# Poseidon.net
KiCad netlist of a schematic drawn in EAGLE
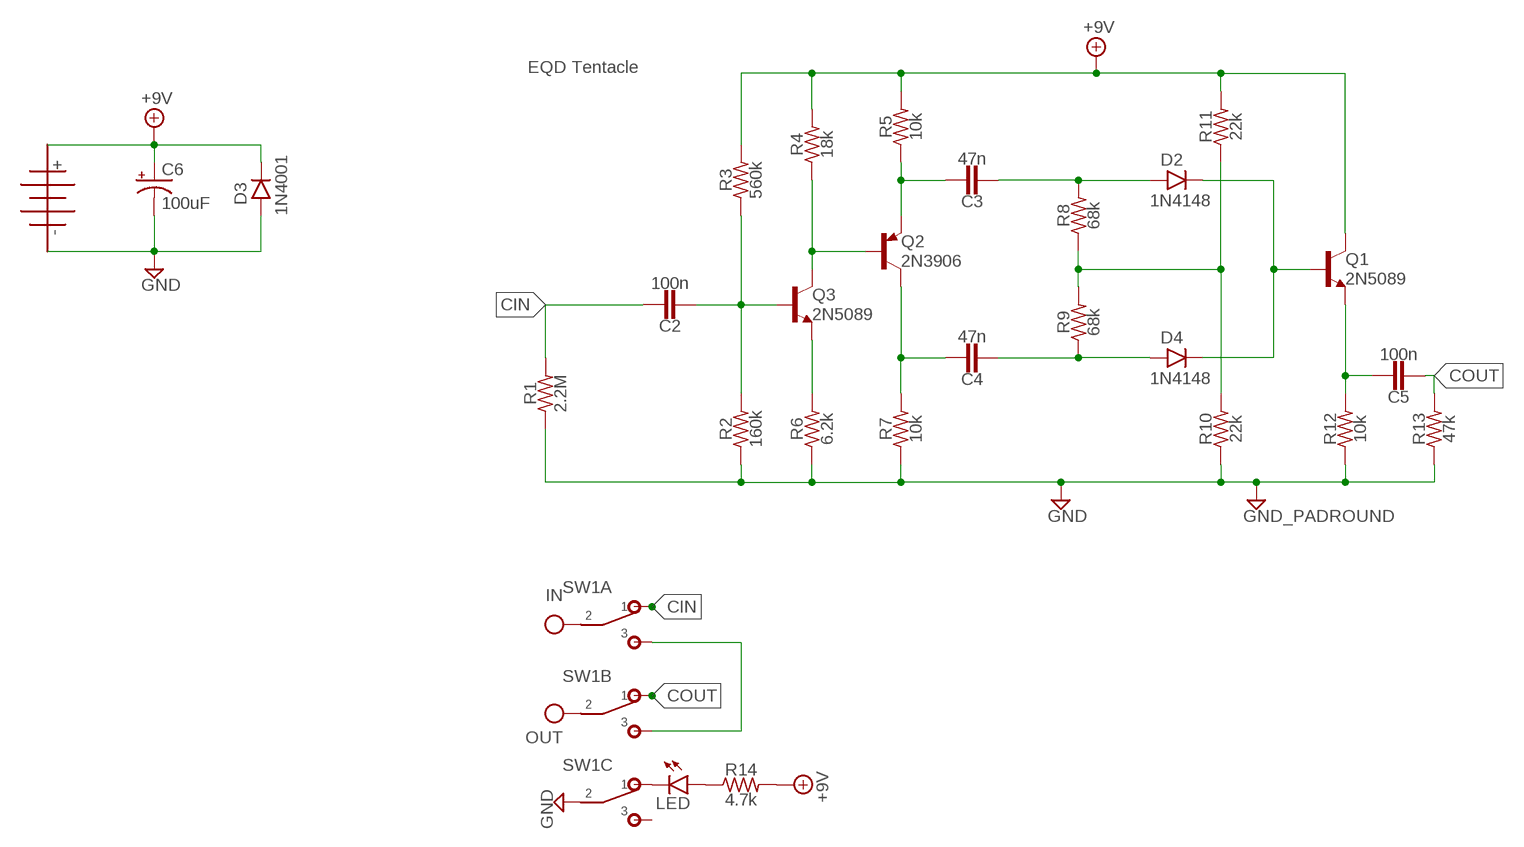
[diagram p0: schematic, sheet 1]

(export (version "E")
  (design (tool "Eeschema 10.0.6"))
  (components
    (comp (ref "C2")
      (value "100n")
      (footprint "eagle-import:0.2_.SML")
      (libsource (lib "eagle-import") (part "CAP.2"))
    )
    (comp (ref "C3")
      (value "47n")
      (footprint "eagle-import:0.2_.SML")
      (libsource (lib "eagle-import") (part "CAP.2"))
    )
    (comp (ref "C4")
      (value "47n")
      (footprint "eagle-import:0.2_.SML")
      (libsource (lib "eagle-import") (part "CAP.2"))
    )
    (comp (ref "C5")
      (value "100n")
      (footprint "eagle-import:0.2_.SML")
      (libsource (lib "eagle-import") (part "CAP.2"))
    )
    (comp (ref "C6")
      (value "100uF")
      (footprint "eagle-import:063_025")
      (libsource (lib "eagle-import") (part "0631"))
    )
    (comp (ref "D2")
      (value "1N4148")
      (footprint "eagle-import:DO35-3")
      (libsource (lib "eagle-import") (part "DO35.3"))
    )
    (comp (ref "D3")
      (value "1N4001")
      (footprint "eagle-import:DO41-3")
      (libsource (lib "eagle-import") (part "DO41.3"))
    )
    (comp (ref "D4")
      (value "1N4148")
      (footprint "eagle-import:DO35-3")
      (libsource (lib "eagle-import") (part "DO35.3"))
    )
    (comp (ref "DC")
      (value "BATTERYBAT2")
      (footprint "eagle-import:BATTERY2")
      (libsource (lib "eagle-import") (part "BATTERYBAT2"))
    )
    (comp (ref "GND")
      (value "GND_PADROUND")
      (footprint "eagle-import:ROUND")
      (libsource (lib "eagle-import") (part "GND_PADROUND"))
    )
    (comp (ref "IN")
      (value "IN")
      (footprint "eagle-import:SQUARE")
      (libsource (lib "eagle-import") (part "IN"))
    )
    (comp (ref "LED")
      (value "LED3MM")
      (footprint "eagle-import:LED3MM")
      (libsource (lib "eagle-import") (part "LED3MM"))
    )
    (comp (ref "OUT")
      (value "OUT")
      (footprint "eagle-import:SQUARE")
      (libsource (lib "eagle-import") (part "OUT"))
    )
    (comp (ref "Q1")
      (value "2N5089")
      (footprint "eagle-import:TO92")
      (libsource (lib "eagle-import") (part "2N5088"))
    )
    (comp (ref "Q2")
      (value "2N3906")
      (footprint "eagle-import:TO92")
      (libsource (lib "eagle-import") (part "2N5087"))
    )
    (comp (ref "Q3")
      (value "2N5089")
      (footprint "eagle-import:TO92")
      (libsource (lib "eagle-import") (part "2N5088"))
    )
    (comp (ref "R1")
      (value "2.2M")
      (footprint "eagle-import:0.3_.B")
      (libsource (lib "eagle-import") (part "R.3B"))
    )
    (comp (ref "R2")
      (value "160k")
      (footprint "eagle-import:0.3_.B")
      (libsource (lib "eagle-import") (part "R.3B"))
    )
    (comp (ref "R3")
      (value "560k")
      (footprint "eagle-import:0.3_.B")
      (libsource (lib "eagle-import") (part "R.3B"))
    )
    (comp (ref "R4")
      (value "18k")
      (footprint "eagle-import:0.3_.B")
      (libsource (lib "eagle-import") (part "R.3B"))
    )
    (comp (ref "R5")
      (value "10k")
      (footprint "eagle-import:0.3_.B")
      (libsource (lib "eagle-import") (part "R.3B"))
    )
    (comp (ref "R6")
      (value "6.2k")
      (footprint "eagle-import:0.3_.B")
      (libsource (lib "eagle-import") (part "R.3B"))
    )
    (comp (ref "R7")
      (value "10k")
      (footprint "eagle-import:0.3_.B")
      (libsource (lib "eagle-import") (part "R.3B"))
    )
    (comp (ref "R8")
      (value "68k")
      (footprint "eagle-import:0.3_.B")
      (libsource (lib "eagle-import") (part "R.3B"))
    )
    (comp (ref "R9")
      (value "68k")
      (footprint "eagle-import:0.3_.B")
      (libsource (lib "eagle-import") (part "R.3B"))
    )
    (comp (ref "R10")
      (value "22k")
      (footprint "eagle-import:0.3_.B")
      (libsource (lib "eagle-import") (part "R.3B"))
    )
    (comp (ref "R11")
      (value "22k")
      (footprint "eagle-import:0.3_.B")
      (libsource (lib "eagle-import") (part "R.3B"))
    )
    (comp (ref "R12")
      (value "10k")
      (footprint "eagle-import:0.3_.B")
      (libsource (lib "eagle-import") (part "R.3B"))
    )
    (comp (ref "R13")
      (value "47k")
      (footprint "eagle-import:0.3_.B")
      (libsource (lib "eagle-import") (part "R.3B"))
    )
    (comp (ref "R14")
      (value "4.7k")
      (footprint "eagle-import:0.3_.B")
      (libsource (lib "eagle-import") (part "R.3B"))
    )
    (comp (ref "SW1")
      (value "3PDT")
      (footprint "eagle-import:3PDT")
      (libsource (lib "eagle-import") (part "3PDT"))
    )
  )
  (nets
    (net (code "1") (name "+9V") (class "Default")
      (node (ref "C6") (pin "+") (pinfunction "+_+") (pintype "passive"))
      (node (ref "D3") (pin "C") (pinfunction "C_C") (pintype "passive"))
      (node (ref "DC") (pin "P$1") (pinfunction "P$1_P$1") (pintype "bidirectional"))
      (node (ref "Q1") (pin "1") (pinfunction "C_1") (pintype "passive"))
      (node (ref "R11") (pin "2") (pinfunction "2_2") (pintype "passive"))
      (node (ref "R14") (pin "2") (pinfunction "2_2") (pintype "passive"))
      (node (ref "R3") (pin "2") (pinfunction "2_2") (pintype "passive"))
      (node (ref "R4") (pin "2") (pinfunction "2_2") (pintype "passive"))
      (node (ref "R5") (pin "2") (pinfunction "2_2") (pintype "passive"))
    )
    (net (code "2") (name "CIN") (class "Default")
      (node (ref "C2") (pin "1") (pinfunction "1_1") (pintype "passive"))
      (node (ref "R1") (pin "2") (pinfunction "2_2") (pintype "passive"))
      (node (ref "SW1") (pin "A1") (pinfunction "1_A1") (pintype "passive"))
    )
    (net (code "3") (name "COUT") (class "Default")
      (node (ref "C5") (pin "2") (pinfunction "2_2") (pintype "passive"))
      (node (ref "R13") (pin "2") (pinfunction "2_2") (pintype "passive"))
      (node (ref "SW1") (pin "B1") (pinfunction "1_B1") (pintype "passive"))
    )
    (net (code "4") (name "GND") (class "Default")
      (node (ref "C6") (pin "-") (pinfunction "-_-") (pintype "passive"))
      (node (ref "D3") (pin "A") (pinfunction "A_A") (pintype "passive"))
      (node (ref "DC") (pin "P$2") (pinfunction "P$2_P$2") (pintype "bidirectional"))
      (node (ref "GND") (pin "1") (pinfunction "GND_1") (pintype "power_in"))
      (node (ref "R1") (pin "1") (pinfunction "1_1") (pintype "passive"))
      (node (ref "R10") (pin "1") (pinfunction "1_1") (pintype "passive"))
      (node (ref "R12") (pin "1") (pinfunction "1_1") (pintype "passive"))
      (node (ref "R13") (pin "1") (pinfunction "1_1") (pintype "passive"))
      (node (ref "R2") (pin "1") (pinfunction "1_1") (pintype "passive"))
      (node (ref "R6") (pin "1") (pinfunction "1_1") (pintype "passive"))
      (node (ref "R7") (pin "1") (pinfunction "1_1") (pintype "passive"))
      (node (ref "SW1") (pin "C2") (pinfunction "2_C2") (pintype "passive"))
    )
    (net (code "5") (name "IN") (class "Default")
      (node (ref "IN") (pin "1") (pinfunction "IN_1") (pintype "power_in"))
      (node (ref "SW1") (pin "A2") (pinfunction "2_A2") (pintype "passive"))
    )
    (net (code "6") (name "Net-(C3-Pad2)") (class "Default")
      (node (ref "C3") (pin "2") (pinfunction "2_2") (pintype "passive"))
      (node (ref "D2") (pin "A") (pinfunction "A_A") (pintype "passive"))
      (node (ref "R8") (pin "2") (pinfunction "2_2") (pintype "passive"))
    )
    (net (code "7") (name "Net-(C4-Pad2)") (class "Default")
      (node (ref "C4") (pin "2") (pinfunction "2_2") (pintype "passive"))
      (node (ref "D4") (pin "A") (pinfunction "A_A") (pintype "passive"))
      (node (ref "R9") (pin "1") (pinfunction "1_1") (pintype "passive"))
    )
    (net (code "8") (name "Net-(LED-C)") (class "Default")
      (node (ref "LED") (pin "K") (pinfunction "C_K") (pintype "passive"))
      (node (ref "SW1") (pin "C1") (pinfunction "1_C1") (pintype "passive"))
    )
    (net (code "9") (name "Net-(LED-PadA)") (class "Default")
      (node (ref "LED") (pin "A") (pinfunction "A_A") (pintype "passive"))
      (node (ref "R14") (pin "1") (pinfunction "1_1") (pintype "passive"))
    )
    (net (code "10") (name "Net-(Q1-B)") (class "Default")
      (node (ref "D2") (pin "C") (pinfunction "C_C") (pintype "passive"))
      (node (ref "D4") (pin "C") (pinfunction "C_C") (pintype "passive"))
      (node (ref "Q1") (pin "2") (pinfunction "B_2") (pintype "passive"))
    )
    (net (code "11") (name "Net-(Q1-E)") (class "Default")
      (node (ref "C5") (pin "1") (pinfunction "1_1") (pintype "passive"))
      (node (ref "Q1") (pin "3") (pinfunction "E_3") (pintype "passive"))
      (node (ref "R12") (pin "2") (pinfunction "2_2") (pintype "passive"))
    )
    (net (code "12") (name "Net-(Q2-B)") (class "Default")
      (node (ref "Q2") (pin "2") (pinfunction "B_2") (pintype "passive"))
      (node (ref "Q3") (pin "1") (pinfunction "C_1") (pintype "passive"))
      (node (ref "R4") (pin "1") (pinfunction "1_1") (pintype "passive"))
    )
    (net (code "13") (name "Net-(Q2-C)") (class "Default")
      (node (ref "C4") (pin "1") (pinfunction "1_1") (pintype "passive"))
      (node (ref "Q2") (pin "1") (pinfunction "C_1") (pintype "passive"))
      (node (ref "R7") (pin "2") (pinfunction "2_2") (pintype "passive"))
    )
    (net (code "14") (name "Net-(Q2-E)") (class "Default")
      (node (ref "C3") (pin "1") (pinfunction "1_1") (pintype "passive"))
      (node (ref "Q2") (pin "3") (pinfunction "E_3") (pintype "passive"))
      (node (ref "R5") (pin "1") (pinfunction "1_1") (pintype "passive"))
    )
    (net (code "15") (name "Net-(Q3-B)") (class "Default")
      (node (ref "C2") (pin "2") (pinfunction "2_2") (pintype "passive"))
      (node (ref "Q3") (pin "2") (pinfunction "B_2") (pintype "passive"))
      (node (ref "R2") (pin "2") (pinfunction "2_2") (pintype "passive"))
      (node (ref "R3") (pin "1") (pinfunction "1_1") (pintype "passive"))
    )
    (net (code "16") (name "Net-(Q3-E)") (class "Default")
      (node (ref "Q3") (pin "3") (pinfunction "E_3") (pintype "passive"))
      (node (ref "R6") (pin "2") (pinfunction "2_2") (pintype "passive"))
    )
    (net (code "17") (name "Net-(R10-Pad2)") (class "Default")
      (node (ref "R10") (pin "2") (pinfunction "2_2") (pintype "passive"))
      (node (ref "R11") (pin "1") (pinfunction "1_1") (pintype "passive"))
      (node (ref "R8") (pin "1") (pinfunction "1_1") (pintype "passive"))
      (node (ref "R9") (pin "2") (pinfunction "2_2") (pintype "passive"))
    )
    (net (code "18") (name "Net-(SW1A-3)") (class "Default")
      (node (ref "SW1") (pin "A3") (pinfunction "3_A3") (pintype "passive"))
      (node (ref "SW1") (pin "B3") (pinfunction "3_B3") (pintype "passive"))
    )
    (net (code "19") (name "OUT") (class "Default")
      (node (ref "OUT") (pin "1") (pinfunction "OUT_1") (pintype "power_in"))
      (node (ref "SW1") (pin "B2") (pinfunction "2_B2") (pintype "passive"))
    )
    (net (code "20") (name "unconnected-(SW1C-3-PadC3)") (class "Default")
      (node (ref "SW1") (pin "C3") (pinfunction "3_C3") (pintype "passive"))
    )
  )
)
